# ESP_SCH.net
KiCad netlist of a schematic drawn in EasyEDA
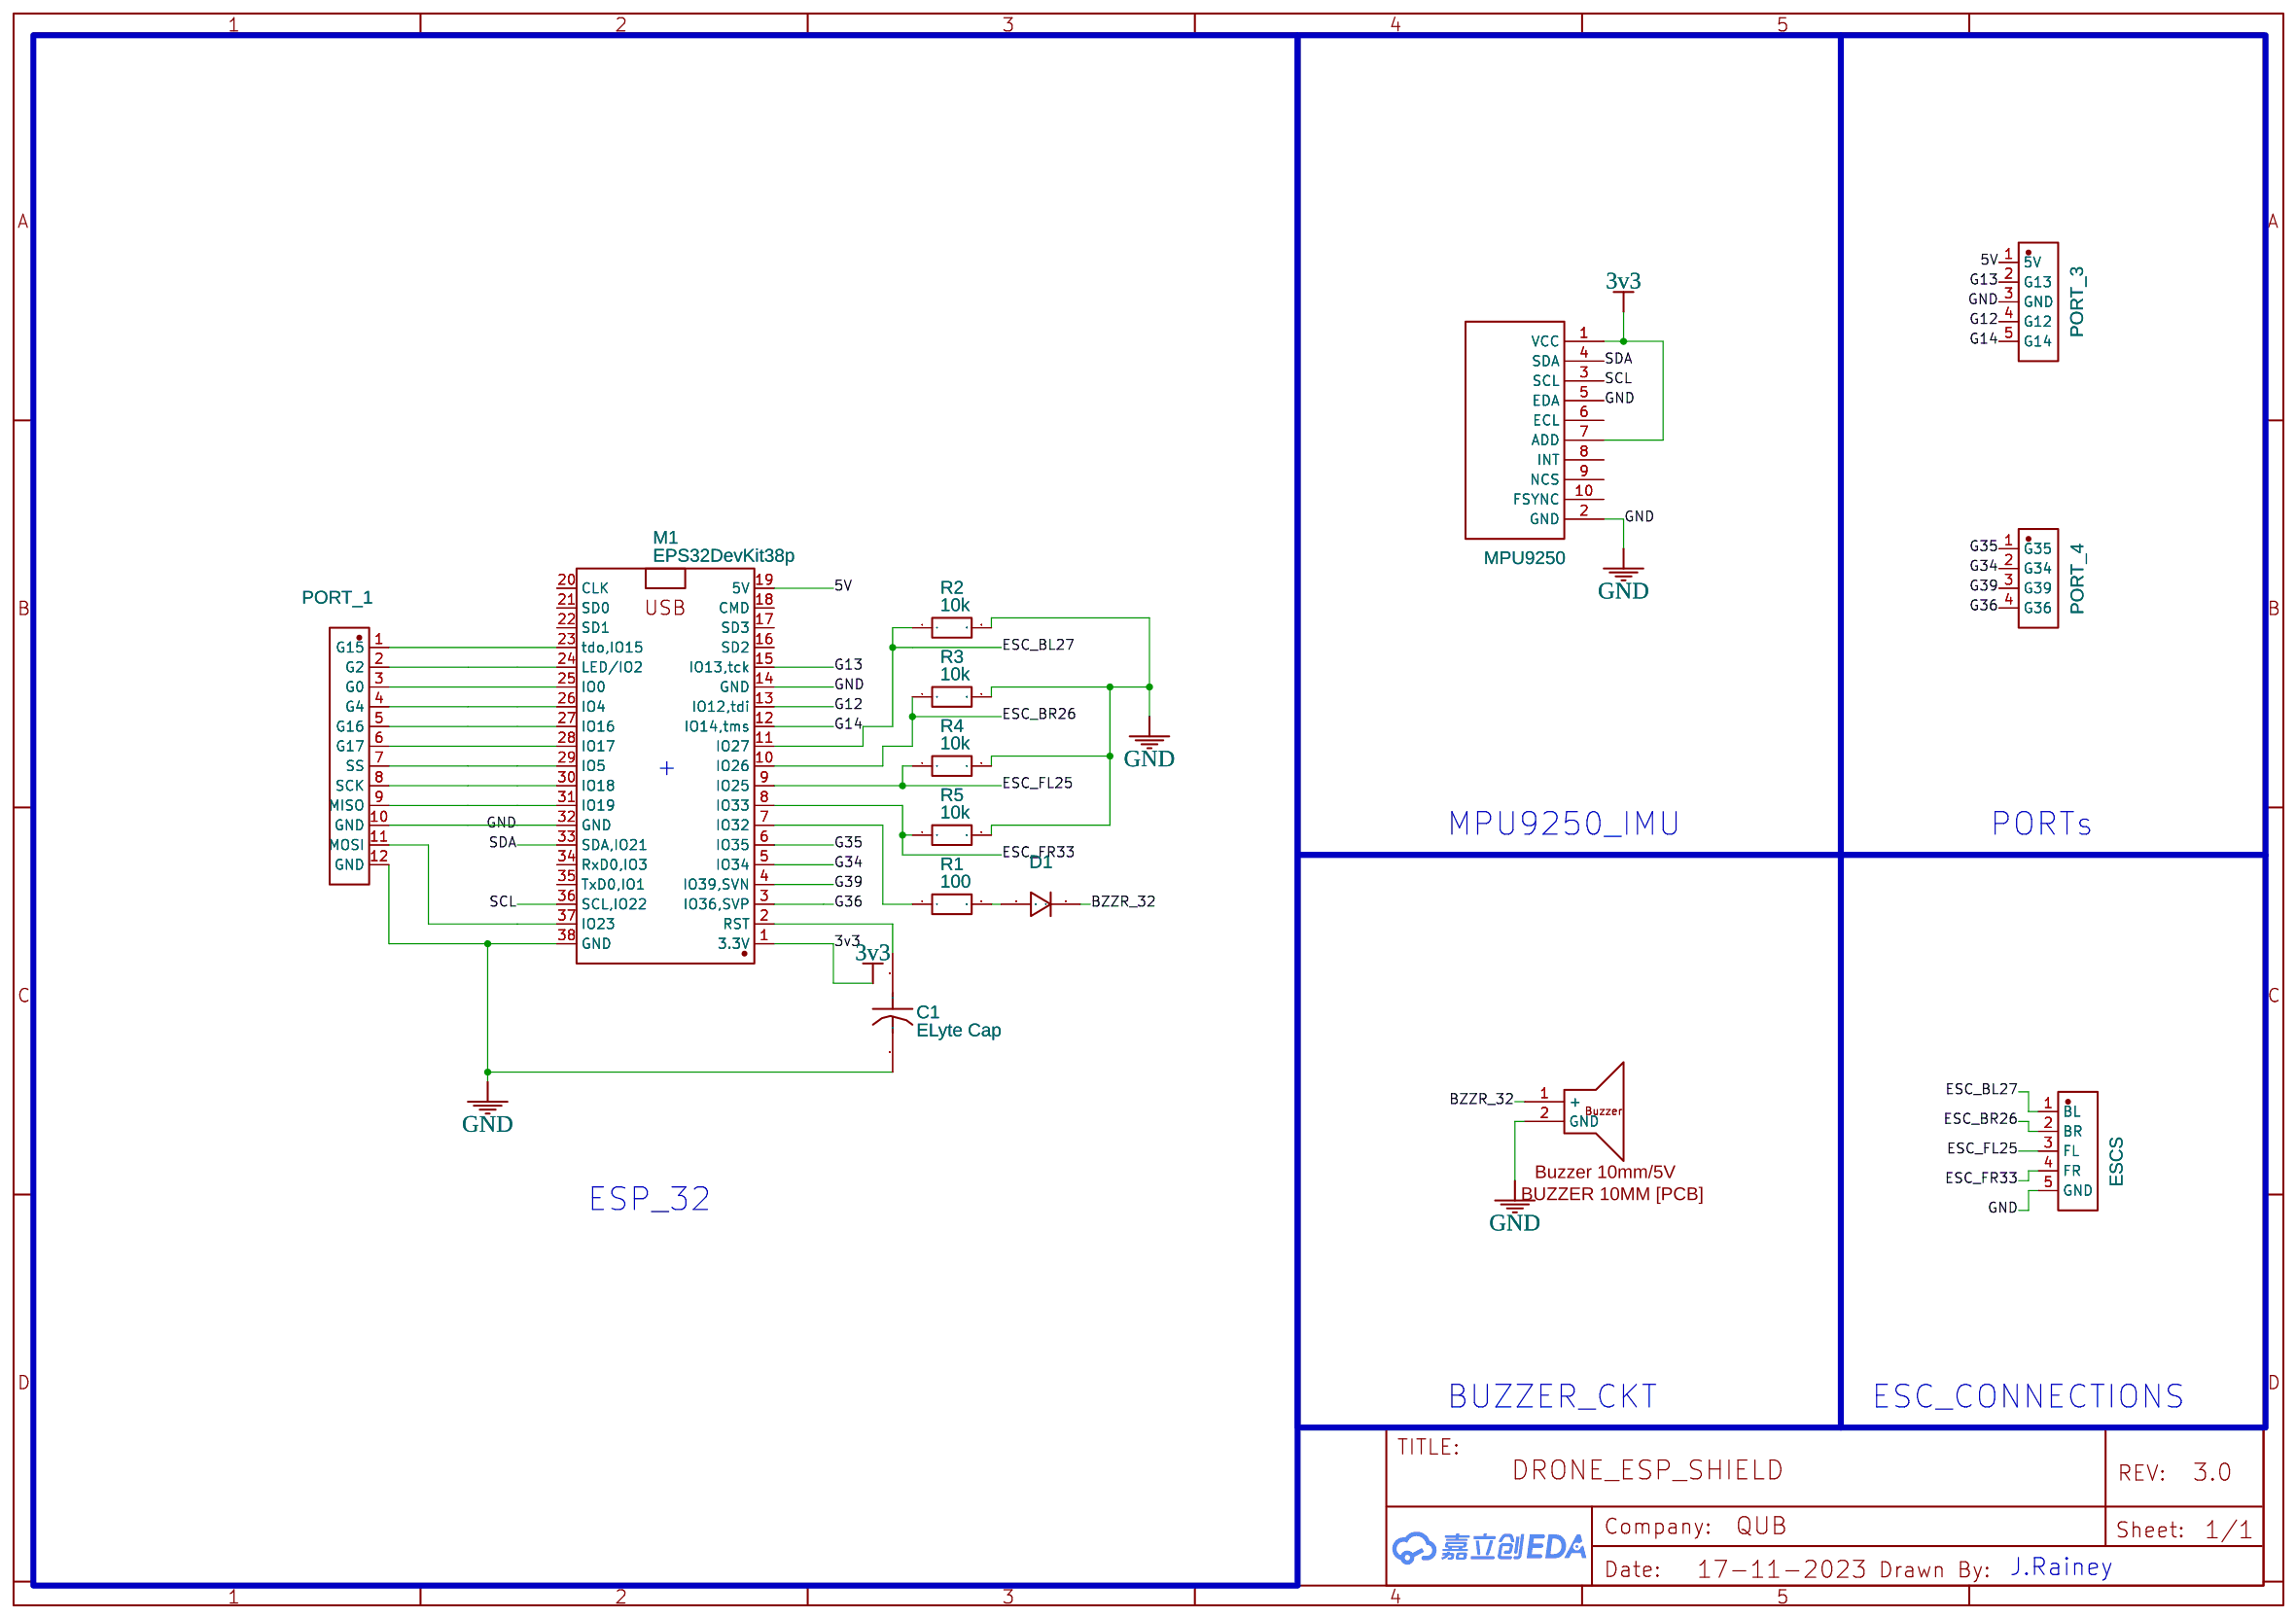
[diagram p0: schematic sheet]

(export (version "E")
  (design (tool "Eeschema 10.0.6"))
  (components
    (comp (ref "BUZZER")
      (value "Buzzer 10mm/5V")
      (fields (field (name "BOM_Manufacturer Part") "BUZZER"))
      (libsource (lib "") (part "Buzzer 10mm/5V"))
    )
    (comp (ref "C1") (value "ELyte Cap") (libsource (lib "") (part "Electrolitic Capacitor")))
    (comp (ref "D1")
      (value "1N4448")
      (fields (field (name "Manufacturer") "ST(先科)"))
      (libsource (lib "") (part "1N4448"))
    )
    (comp (ref "ESCS")
      (value "PORT_3")
      (fields (field (name "Manufacturer Part") "DS1002-03-1x5131") (field (name "Manufacturer") "CONNFLY"))
      (libsource (lib "") (part "DS1002-03-1X5131"))
    )
    (comp (ref "M1") (value "EPS32DevKit38p") (libsource (lib "") (part "EPS32DevKit38p")))
    (comp (ref "MPU9250") (value "MPU9250") (libsource (lib "") (part "MPU9250 MODULE")))
    (comp (ref "PORT_1")
      (value "ZX-PM2.54-1-12PY")
      (fields (field (name "Manufacturer") "Megastar(兆星)"))
      (libsource (lib "") (part "ZX-PM2.54-1-12PY"))
    )
    (comp (ref "PORT_3")
      (value "PORT_3")
      (fields (field (name "Manufacturer Part") "DS1002-03-1x5131") (field (name "Manufacturer") "CONNFLY"))
      (libsource (lib "") (part "DS1002-03-1X5131_1"))
    )
    (comp (ref "PORT_4")
      (value "0022285044")
      (fields (field (name "BOM_Supplier Part") "C9900016049"))
      (libsource (lib "") (part "0022285044"))
    )
    (comp (ref "R1") (value "100") (libsource (lib "") (part "R_AXIAL-0.4_EU")))
    (comp (ref "R2") (value "10k") (libsource (lib "") (part "R_AXIAL-0.4_EU")))
    (comp (ref "R3") (value "10k") (libsource (lib "") (part "R_AXIAL-0.4_EU")))
    (comp (ref "R4") (value "10k") (libsource (lib "") (part "R_AXIAL-0.4_EU")))
    (comp (ref "R5") (value "10k") (libsource (lib "") (part "R_AXIAL-0.4_EU")))
  )
  (nets
    (net (code "1") (name "/5V") (class "Default")
      (node (ref "M1") (pin "19") (pinfunction "5V_19") (pintype "unspecified"))
      (node (ref "PORT_3") (pin "1") (pinfunction "5V_1") (pintype "unspecified"))
    )
    (net (code "2") (name "/BZZR_32") (class "Default")
      (node (ref "BUZZER") (pin "1") (pinfunction "+_1") (pintype "unspecified"))
      (node (ref "D1") (pin "2") (pinfunction "K_2") (pintype "unspecified"))
    )
    (net (code "3") (name "/ESC_BL27") (class "Default")
      (node (ref "ESCS") (pin "1") (pinfunction "BL_1") (pintype "unspecified"))
      (node (ref "M1") (pin "11") (pinfunction "IO27_11") (pintype "unspecified"))
      (node (ref "R2") (pin "1") (pinfunction "1_1") (pintype "unspecified"))
    )
    (net (code "4") (name "/ESC_BR26") (class "Default")
      (node (ref "ESCS") (pin "2") (pinfunction "BR_2") (pintype "unspecified"))
      (node (ref "M1") (pin "10") (pinfunction "IO26_10") (pintype "unspecified"))
      (node (ref "R3") (pin "1") (pinfunction "1_1") (pintype "unspecified"))
    )
    (net (code "5") (name "/ESC_FL25") (class "Default")
      (node (ref "ESCS") (pin "3") (pinfunction "FL_3") (pintype "unspecified"))
      (node (ref "M1") (pin "9") (pinfunction "IO25_9") (pintype "unspecified"))
      (node (ref "R4") (pin "1") (pinfunction "1_1") (pintype "unspecified"))
    )
    (net (code "6") (name "/ESC_FR33") (class "Default")
      (node (ref "ESCS") (pin "4") (pinfunction "FR_4") (pintype "unspecified"))
      (node (ref "M1") (pin "8") (pinfunction "IO33_8") (pintype "unspecified"))
      (node (ref "R5") (pin "1") (pinfunction "1_1") (pintype "unspecified"))
    )
    (net (code "7") (name "/G12") (class "Default")
      (node (ref "M1") (pin "13") (pinfunction "IO12,tdi_13") (pintype "unspecified"))
      (node (ref "PORT_3") (pin "4") (pinfunction "G12_4") (pintype "unspecified"))
    )
    (net (code "8") (name "/G13") (class "Default")
      (node (ref "M1") (pin "15") (pinfunction "IO13,tck_15") (pintype "unspecified"))
      (node (ref "PORT_3") (pin "2") (pinfunction "G13_2") (pintype "unspecified"))
    )
    (net (code "9") (name "/G14") (class "Default")
      (node (ref "M1") (pin "12") (pinfunction "IO14,tms_12") (pintype "unspecified"))
      (node (ref "PORT_3") (pin "5") (pinfunction "G14_5") (pintype "unspecified"))
    )
    (net (code "10") (name "/G34") (class "Default")
      (node (ref "M1") (pin "5") (pinfunction "IO34_5") (pintype "unspecified"))
      (node (ref "PORT_4") (pin "2") (pinfunction "G34_2") (pintype "unspecified"))
    )
    (net (code "11") (name "/G35") (class "Default")
      (node (ref "M1") (pin "6") (pinfunction "IO35_6") (pintype "unspecified"))
      (node (ref "PORT_4") (pin "1") (pinfunction "G35_1") (pintype "unspecified"))
    )
    (net (code "12") (name "/G36") (class "Default")
      (node (ref "M1") (pin "3") (pinfunction "IO36,SVP_3") (pintype "unspecified"))
      (node (ref "PORT_4") (pin "4") (pinfunction "G36_4") (pintype "unspecified"))
    )
    (net (code "13") (name "/G39") (class "Default")
      (node (ref "M1") (pin "4") (pinfunction "IO39,SVN_4") (pintype "unspecified"))
      (node (ref "PORT_4") (pin "3") (pinfunction "G39_3") (pintype "unspecified"))
    )
    (net (code "14") (name "/SCL") (class "Default")
      (node (ref "M1") (pin "36") (pinfunction "SCL,IO22_36") (pintype "unspecified"))
      (node (ref "MPU9250") (pin "3") (pinfunction "SCL_3") (pintype "bidirectional"))
    )
    (net (code "15") (name "/SDA") (class "Default")
      (node (ref "M1") (pin "33") (pinfunction "SDA,IO21_33") (pintype "unspecified"))
      (node (ref "MPU9250") (pin "4") (pinfunction "SDA_4") (pintype "bidirectional"))
    )
    (net (code "16") (name "3v3") (class "Default")
      (node (ref "M1") (pin "1") (pinfunction "3.3V_1") (pintype "unspecified"))
      (node (ref "MPU9250") (pin "1") (pinfunction "VCC_1") (pintype "passive"))
      (node (ref "MPU9250") (pin "7") (pinfunction "ADD_7") (pintype "bidirectional"))
    )
    (net (code "17") (name "GND") (class "Default")
      (node (ref "BUZZER") (pin "2") (pinfunction "GND_2") (pintype "unspecified"))
      (node (ref "C1") (pin "2") (pinfunction "2_2") (pintype "unspecified"))
      (node (ref "ESCS") (pin "5") (pinfunction "GND_5") (pintype "unspecified"))
      (node (ref "M1") (pin "14") (pinfunction "GND_14") (pintype "unspecified"))
      (node (ref "M1") (pin "32") (pinfunction "GND_32") (pintype "unspecified"))
      (node (ref "M1") (pin "38") (pinfunction "GND_38") (pintype "unspecified"))
      (node (ref "MPU9250") (pin "2") (pinfunction "GND_2") (pintype "passive"))
      (node (ref "MPU9250") (pin "5") (pinfunction "EDA_5") (pintype "bidirectional"))
      (node (ref "PORT_1") (pin "10") (pinfunction "GND_10") (pintype "unspecified"))
      (node (ref "PORT_1") (pin "12") (pinfunction "GND_12") (pintype "unspecified"))
      (node (ref "PORT_3") (pin "3") (pinfunction "GND_3") (pintype "unspecified"))
      (node (ref "R2") (pin "2") (pinfunction "2_2") (pintype "unspecified"))
      (node (ref "R3") (pin "2") (pinfunction "2_2") (pintype "unspecified"))
      (node (ref "R4") (pin "2") (pinfunction "2_2") (pintype "unspecified"))
      (node (ref "R5") (pin "2") (pinfunction "2_2") (pintype "unspecified"))
    )
    (net (code "18") (name "Net-(D1-A)") (class "Default")
      (node (ref "D1") (pin "1") (pinfunction "A_1") (pintype "unspecified"))
      (node (ref "R1") (pin "2") (pinfunction "2_2") (pintype "unspecified"))
    )
    (net (code "19") (name "Net-(M1-IO0)") (class "Default")
      (node (ref "M1") (pin "25") (pinfunction "IO0_25") (pintype "unspecified"))
      (node (ref "PORT_1") (pin "3") (pinfunction "G0_3") (pintype "unspecified"))
    )
    (net (code "20") (name "Net-(M1-IO4)") (class "Default")
      (node (ref "M1") (pin "26") (pinfunction "IO4_26") (pintype "unspecified"))
      (node (ref "PORT_1") (pin "4") (pinfunction "G4_4") (pintype "unspecified"))
    )
    (net (code "21") (name "Net-(M1-IO5)") (class "Default")
      (node (ref "M1") (pin "29") (pinfunction "IO5_29") (pintype "unspecified"))
      (node (ref "PORT_1") (pin "7") (pinfunction "SS_7") (pintype "unspecified"))
    )
    (net (code "22") (name "Net-(M1-IO16)") (class "Default")
      (node (ref "M1") (pin "27") (pinfunction "IO16_27") (pintype "unspecified"))
      (node (ref "PORT_1") (pin "5") (pinfunction "G16_5") (pintype "unspecified"))
    )
    (net (code "23") (name "Net-(M1-IO17)") (class "Default")
      (node (ref "M1") (pin "28") (pinfunction "IO17_28") (pintype "unspecified"))
      (node (ref "PORT_1") (pin "6") (pinfunction "G17_6") (pintype "unspecified"))
    )
    (net (code "24") (name "Net-(M1-IO18)") (class "Default")
      (node (ref "M1") (pin "30") (pinfunction "IO18_30") (pintype "unspecified"))
      (node (ref "PORT_1") (pin "8") (pinfunction "SCK_8") (pintype "unspecified"))
    )
    (net (code "25") (name "Net-(M1-IO19)") (class "Default")
      (node (ref "M1") (pin "31") (pinfunction "IO19_31") (pintype "unspecified"))
      (node (ref "PORT_1") (pin "9") (pinfunction "MISO_9") (pintype "unspecified"))
    )
    (net (code "26") (name "Net-(M1-IO23)") (class "Default")
      (node (ref "M1") (pin "37") (pinfunction "IO23_37") (pintype "unspecified"))
      (node (ref "PORT_1") (pin "11") (pinfunction "MOSI_11") (pintype "unspecified"))
    )
    (net (code "27") (name "Net-(M1-IO32)") (class "Default")
      (node (ref "M1") (pin "7") (pinfunction "IO32_7") (pintype "unspecified"))
      (node (ref "R1") (pin "1") (pinfunction "1_1") (pintype "unspecified"))
    )
    (net (code "28") (name "Net-(M1-LED{slash}IO2)") (class "Default")
      (node (ref "M1") (pin "24") (pinfunction "LED/IO2_24") (pintype "unspecified"))
      (node (ref "PORT_1") (pin "2") (pinfunction "G2_2") (pintype "unspecified"))
    )
    (net (code "29") (name "Net-(M1-RST)") (class "Default")
      (node (ref "C1") (pin "1") (pinfunction "1_1") (pintype "unspecified"))
      (node (ref "M1") (pin "2") (pinfunction "RST_2") (pintype "unspecified"))
    )
    (net (code "30") (name "Net-(M1-tdo,IO15)") (class "Default")
      (node (ref "M1") (pin "23") (pinfunction "tdo,IO15_23") (pintype "unspecified"))
      (node (ref "PORT_1") (pin "1") (pinfunction "G15_1") (pintype "unspecified"))
    )
    (net (code "31") (name "unconnected-(M1-CLK-Pad20)") (class "Default")
      (node (ref "M1") (pin "20") (pinfunction "CLK_20") (pintype "unspecified"))
    )
    (net (code "32") (name "unconnected-(M1-CMD-Pad18)") (class "Default")
      (node (ref "M1") (pin "18") (pinfunction "CMD_18") (pintype "unspecified"))
    )
    (net (code "33") (name "unconnected-(M1-RxD0,IO3-Pad34)") (class "Default")
      (node (ref "M1") (pin "34") (pinfunction "RxD0,IO3_34") (pintype "unspecified"))
    )
    (net (code "34") (name "unconnected-(M1-SD0-Pad21)") (class "Default")
      (node (ref "M1") (pin "21") (pinfunction "SD0_21") (pintype "unspecified"))
    )
    (net (code "35") (name "unconnected-(M1-SD1-Pad22)") (class "Default")
      (node (ref "M1") (pin "22") (pinfunction "SD1_22") (pintype "unspecified"))
    )
    (net (code "36") (name "unconnected-(M1-SD2-Pad16)") (class "Default")
      (node (ref "M1") (pin "16") (pinfunction "SD2_16") (pintype "unspecified"))
    )
    (net (code "37") (name "unconnected-(M1-SD3-Pad17)") (class "Default")
      (node (ref "M1") (pin "17") (pinfunction "SD3_17") (pintype "unspecified"))
    )
    (net (code "38") (name "unconnected-(M1-TxD0,IO1-Pad35)") (class "Default")
      (node (ref "M1") (pin "35") (pinfunction "TxD0,IO1_35") (pintype "unspecified"))
    )
    (net (code "39") (name "unconnected-(MPU9250-ECL-Pad6)") (class "Default")
      (node (ref "MPU9250") (pin "6") (pinfunction "ECL_6") (pintype "bidirectional"))
    )
    (net (code "40") (name "unconnected-(MPU9250-FSYNC-Pad10)") (class "Default")
      (node (ref "MPU9250") (pin "10") (pinfunction "FSYNC_10") (pintype "bidirectional"))
    )
    (net (code "41") (name "unconnected-(MPU9250-INT-Pad8)") (class "Default")
      (node (ref "MPU9250") (pin "8") (pinfunction "INT_8") (pintype "bidirectional"))
    )
    (net (code "42") (name "unconnected-(MPU9250-NCS-Pad9)") (class "Default")
      (node (ref "MPU9250") (pin "9") (pinfunction "NCS_9") (pintype "bidirectional"))
    )
  )
)
